# MainBoard_V100_SD.net
KiCad netlist of a schematic drawn in Altium Designer
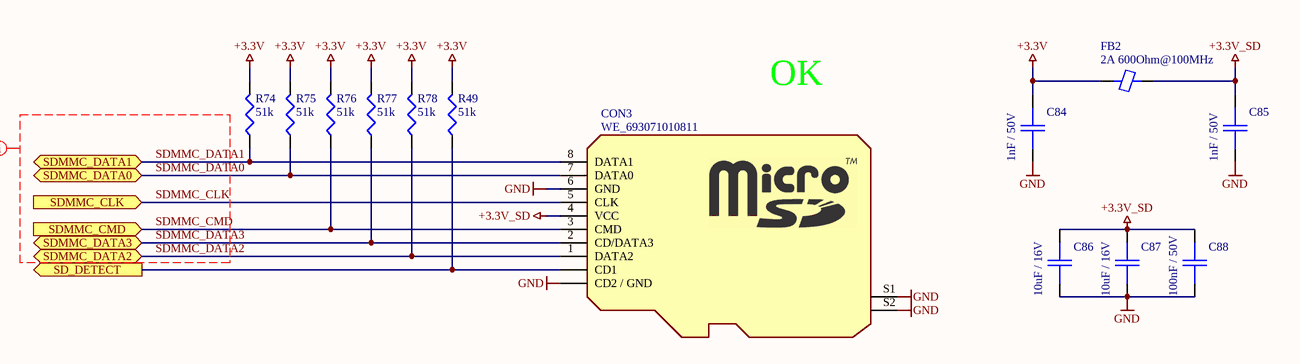
[diagram p0: MainBoard_V100_SD.SchDoc]

(export (version "E")
  (design (tool "Eeschema 10.0.6"))
  (components
    (comp (ref "C84")
      (value "1nF / 50V")
      (footprint "0805_C")
      (description "1nF 50V X7R")
      (fields (field (name "PART NUMBER") "SMD0805-1nF-50V"))
      (libsource (lib "ALTIUM_DB_LIB") (part "CAP_NONPOL"))
    )
    (comp (ref "C85")
      (value "1nF / 50V")
      (footprint "0805_C")
      (description "1nF 50V X7R")
      (fields (field (name "PART NUMBER") "SMD0805-1nF-50V"))
      (libsource (lib "ALTIUM_DB_LIB") (part "CAP_NONPOL"))
    )
    (comp (ref "C86")
      (value "10uF / 16V")
      (footprint "0805_C")
      (description "10uF 16V X5R")
      (fields (field (name "PART NUMBER") "SMD0805-10uF-16V"))
      (libsource (lib "ALTIUM_DB_LIB") (part "CAP_NONPOL"))
    )
    (comp (ref "C87")
      (value "10uF / 16V")
      (footprint "0805_C")
      (description "10uF 16V X5R")
      (fields (field (name "PART NUMBER") "SMD0805-10uF-16V"))
      (libsource (lib "ALTIUM_DB_LIB") (part "CAP_NONPOL"))
    )
    (comp (ref "C88")
      (value "100nF / 50V")
      (footprint "0805_C")
      (description "100nF 50V X7R")
      (fields (field (name "PART NUMBER") "SMD0805-100nF-50V"))
      (libsource (lib "ALTIUM_DB_LIB") (part "CAP_NONPOL"))
    )
    (comp (ref "CON3")
      (value "WE_693071010811")
      (footprint "T_Wurth_693071010811")
      (description "Memory Card Connectors WR-CRD SD Micro Card 8Pin Push & Push")
      (libsource (lib "ALTIUM_DB_LIB") (part "MICROSD_WE_693071010811"))
    )
    (comp (ref "FB2")
      (value "2A 600Ohm@100MHz")
      (footprint "0805_FB")
      (description "Ferrite bead 2A 600Ohm@100MHz")
      (fields (field (name "PART NUMBER") "LCBB-601 SMD"))
      (libsource (lib "ALTIUM_DB_LIB") (part "FERRITE_BEAD"))
    )
    (comp (ref "R49")
      (value "51k")
      (footprint "0805")
      (description "51k 0805 0.125W 5%")
      (fields (field (name "PART NUMBER") "SMD0805-51k 5%"))
      (libsource (lib "ALTIUM_DB_LIB") (part "RESISTOR"))
    )
    (comp (ref "R74")
      (value "51k")
      (footprint "0805")
      (description "51k 0805 0.125W 5%")
      (fields (field (name "PART NUMBER") "SMD0805-51k 5%"))
      (libsource (lib "ALTIUM_DB_LIB") (part "RESISTOR"))
    )
    (comp (ref "R75")
      (value "51k")
      (footprint "0805")
      (description "51k 0805 0.125W 5%")
      (fields (field (name "PART NUMBER") "SMD0805-51k 5%"))
      (libsource (lib "ALTIUM_DB_LIB") (part "RESISTOR"))
    )
    (comp (ref "R76")
      (value "51k")
      (footprint "0805")
      (description "51k 0805 0.125W 5%")
      (fields (field (name "PART NUMBER") "SMD0805-51k 5%"))
      (libsource (lib "ALTIUM_DB_LIB") (part "RESISTOR"))
    )
    (comp (ref "R77")
      (value "51k")
      (footprint "0805")
      (description "51k 0805 0.125W 5%")
      (fields (field (name "PART NUMBER") "SMD0805-51k 5%"))
      (libsource (lib "ALTIUM_DB_LIB") (part "RESISTOR"))
    )
    (comp (ref "R78")
      (value "51k")
      (footprint "0805")
      (description "51k 0805 0.125W 5%")
      (fields (field (name "PART NUMBER") "SMD0805-51k 5%"))
      (libsource (lib "ALTIUM_DB_LIB") (part "RESISTOR"))
    )
  )
  (nets
    (net (code "1") (name "+3.3V") (class "Default")
      (node (ref "C84") (pin "1") (pintype "passive"))
      (node (ref "FB2") (pin "1") (pinfunction "1_1") (pintype "passive"))
      (node (ref "R49") (pin "2") (pintype "passive"))
      (node (ref "R74") (pin "2") (pintype "passive"))
      (node (ref "R75") (pin "2") (pintype "passive"))
      (node (ref "R76") (pin "2") (pintype "passive"))
      (node (ref "R77") (pin "2") (pintype "passive"))
      (node (ref "R78") (pin "2") (pintype "passive"))
    )
    (net (code "2") (name "+3.3V_SD") (class "Default")
      (node (ref "C85") (pin "1") (pintype "passive"))
      (node (ref "C86") (pin "2") (pintype "passive"))
      (node (ref "C87") (pin "2") (pintype "passive"))
      (node (ref "C88") (pin "1") (pintype "passive"))
      (node (ref "CON3") (pin "4") (pinfunction "VCC_4") (pintype "passive"))
      (node (ref "FB2") (pin "2") (pinfunction "2_2") (pintype "passive"))
    )
    (net (code "3") (name "/SDMMC_CLK") (class "Default")
      (node (ref "CON3") (pin "5") (pinfunction "CLK_5") (pintype "power_in"))
    )
    (net (code "4") (name "/SDMMC_CMD") (class "Default")
      (node (ref "CON3") (pin "3") (pinfunction "CMD_3") (pintype "passive"))
      (node (ref "R76") (pin "1") (pintype "passive"))
    )
    (net (code "5") (name "/SDMMC_DATA0") (class "Default")
      (node (ref "CON3") (pin "7") (pinfunction "DATA0_7") (pintype "power_in"))
      (node (ref "R75") (pin "1") (pintype "passive"))
    )
    (net (code "6") (name "/SDMMC_DATA1") (class "Default")
      (node (ref "CON3") (pin "8") (pinfunction "DATA1_8") (pintype "power_in"))
      (node (ref "R74") (pin "1") (pintype "passive"))
    )
    (net (code "7") (name "/SDMMC_DATA2") (class "Default")
      (node (ref "CON3") (pin "1") (pinfunction "DATA2_1") (pintype "power_in"))
      (node (ref "R78") (pin "1") (pintype "passive"))
    )
    (net (code "8") (name "/SDMMC_DATA3") (class "Default")
      (node (ref "CON3") (pin "2") (pinfunction "CD/DATA3_2") (pintype "passive"))
      (node (ref "R77") (pin "1") (pintype "passive"))
    )
    (net (code "9") (name "/SD_DETECT") (class "Default")
      (node (ref "CON3") (pin "CD1") (pinfunction "CD1_CD1") (pintype "power_in"))
      (node (ref "R49") (pin "1") (pintype "passive"))
    )
    (net (code "10") (name "GND") (class "Default")
      (node (ref "C84") (pin "2") (pintype "passive"))
      (node (ref "C85") (pin "2") (pintype "passive"))
      (node (ref "C86") (pin "1") (pintype "passive"))
      (node (ref "C87") (pin "1") (pintype "passive"))
      (node (ref "C88") (pin "2") (pintype "passive"))
      (node (ref "CON3") (pin "6") (pinfunction "GND_6") (pintype "power_in"))
      (node (ref "CON3") (pin "CD2") (pinfunction "CD2_/_GND_CD2") (pintype "power_in"))
      (node (ref "CON3") (pin "S1") (pinfunction "S_S1") (pintype "passive"))
      (node (ref "CON3") (pin "S2") (pinfunction "S_S2") (pintype "passive"))
    )
  )
)
